# Mini_Arduino_3mm.net
KiCad netlist of a schematic drawn in EAGLE
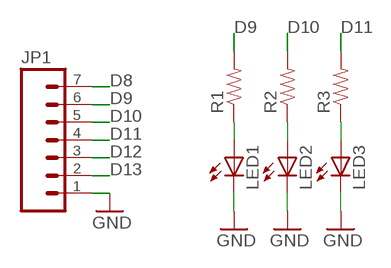
[diagram p0: schematic, sheet 1]

(export (version "E")
  (design (tool "Eeschema 10.0.6"))
  (components
    (comp (ref "JP1")
      (value "M07")
      (footprint "eagle-import:1X07")
      (libsource (lib "eagle-import") (part "M07"))
    )
    (comp (ref "LED1")
      (value "LED3MM")
      (footprint "eagle-import:LED3MM")
      (libsource (lib "eagle-import") (part "LED3MM"))
    )
    (comp (ref "LED2")
      (value "LED3MM")
      (footprint "eagle-import:LED3MM")
      (libsource (lib "eagle-import") (part "LED3MM"))
    )
    (comp (ref "LED3")
      (value "LED3MM")
      (footprint "eagle-import:LED3MM")
      (libsource (lib "eagle-import") (part "LED3MM"))
    )
    (comp (ref "R1")
      (value "RESISTORAXIAL-0.3")
      (footprint "eagle-import:AXIAL-0.3")
      (libsource (lib "eagle-import") (part "RESISTORAXIAL-0.3"))
    )
    (comp (ref "R2")
      (value "RESISTORAXIAL-0.3")
      (footprint "eagle-import:AXIAL-0.3")
      (libsource (lib "eagle-import") (part "RESISTORAXIAL-0.3"))
    )
    (comp (ref "R3")
      (value "RESISTORAXIAL-0.3")
      (footprint "eagle-import:AXIAL-0.3")
      (libsource (lib "eagle-import") (part "RESISTORAXIAL-0.3"))
    )
  )
  (nets
    (net (code "1") (name "/D8") (class "Default")
      (node (ref "JP1") (pin "7") (pinfunction "7_7") (pintype "passive"))
    )
    (net (code "2") (name "/D9") (class "Default")
      (node (ref "JP1") (pin "6") (pinfunction "6_6") (pintype "passive"))
      (node (ref "R1") (pin "P$2") (pinfunction "2_P$2") (pintype "passive"))
    )
    (net (code "3") (name "/D10") (class "Default")
      (node (ref "JP1") (pin "5") (pinfunction "5_5") (pintype "passive"))
      (node (ref "R2") (pin "P$2") (pinfunction "2_P$2") (pintype "passive"))
    )
    (net (code "4") (name "/D11") (class "Default")
      (node (ref "JP1") (pin "4") (pinfunction "4_4") (pintype "passive"))
      (node (ref "R3") (pin "P$2") (pinfunction "2_P$2") (pintype "passive"))
    )
    (net (code "5") (name "/D12") (class "Default")
      (node (ref "JP1") (pin "3") (pinfunction "3_3") (pintype "passive"))
    )
    (net (code "6") (name "/D13") (class "Default")
      (node (ref "JP1") (pin "2") (pinfunction "2_2") (pintype "passive"))
    )
    (net (code "7") (name "GND") (class "Default")
      (node (ref "JP1") (pin "1") (pinfunction "1_1") (pintype "passive"))
      (node (ref "LED1") (pin "K") (pinfunction "C_K") (pintype "passive"))
      (node (ref "LED2") (pin "K") (pinfunction "C_K") (pintype "passive"))
      (node (ref "LED3") (pin "K") (pinfunction "C_K") (pintype "passive"))
    )
    (net (code "8") (name "Net-(R1-1)") (class "Default")
      (node (ref "LED1") (pin "A") (pinfunction "A_A") (pintype "passive"))
      (node (ref "R1") (pin "P$1") (pinfunction "1_P$1") (pintype "passive"))
    )
    (net (code "9") (name "Net-(R2-1)") (class "Default")
      (node (ref "LED2") (pin "A") (pinfunction "A_A") (pintype "passive"))
      (node (ref "R2") (pin "P$1") (pinfunction "1_P$1") (pintype "passive"))
    )
    (net (code "10") (name "Net-(R3-1)") (class "Default")
      (node (ref "LED3") (pin "A") (pinfunction "A_A") (pintype "passive"))
      (node (ref "R3") (pin "P$1") (pinfunction "1_P$1") (pintype "passive"))
    )
  )
)
